# Sheet1.net
KiCad netlist of a schematic drawn in Altium Designer
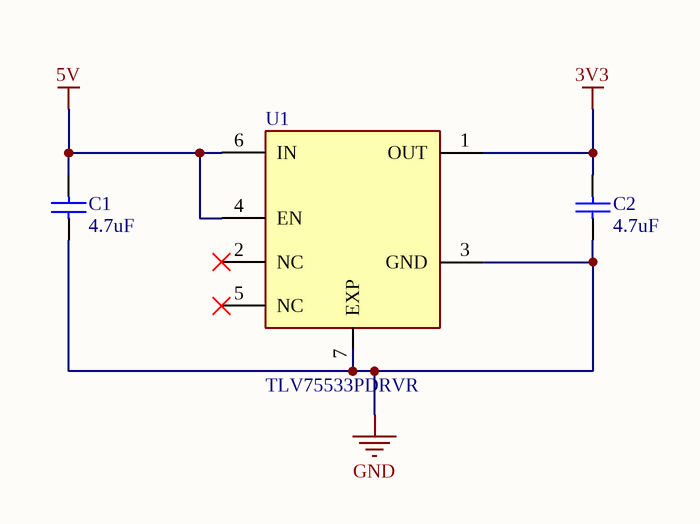
[diagram p0: Sheet1.SchDoc]

(export (version "E")
  (design (tool "Eeschema 10.0.6"))
  (components
    (comp (ref "C1")
      (value "4.7uF")
      (footprint "CAP_0402")
      (description "Capacitor SMD 0402 Generic, X5R or X7R")
      (libsource (lib "AndreiLib") (part "CAP_0402"))
    )
    (comp (ref "C2")
      (value "4.7uF")
      (footprint "CAP_0402")
      (description "Capacitor SMD 0402 Generic, X5R or X7R")
      (libsource (lib "AndreiLib") (part "CAP_0402"))
    )
    (comp (ref "U1")
      (value "TLV75533PDRVR")
      (footprint "TLV75533PDRVR")
      (description "500mA high-PSRR low-IQ low-dropout voltage regulator with enable 6-WSON -40 to 125")
      (fields (field (name "MANUFACTURER") "Texas Instruments"))
      (libsource (lib "AndreiLib") (part "TLV75533PDRVR"))
    )
  )
  (nets
    (net (code "1") (name "3V3") (class "Default")
      (node (ref "C2") (pin "2") (pintype "passive"))
      (node (ref "U1") (pin "1") (pinfunction "OUT_1") (pintype "passive"))
    )
    (net (code "2") (name "5V") (class "Default")
      (node (ref "C1") (pin "1") (pintype "passive"))
      (node (ref "U1") (pin "4") (pinfunction "EN_4") (pintype "passive"))
      (node (ref "U1") (pin "6") (pinfunction "IN_6") (pintype "passive"))
    )
    (net (code "3") (name "GND") (class "Default")
      (node (ref "C1") (pin "2") (pintype "passive"))
      (node (ref "C2") (pin "1") (pintype "passive"))
      (node (ref "U1") (pin "3") (pinfunction "GND_3") (pintype "power_in"))
      (node (ref "U1") (pin "7") (pinfunction "EXP_7") (pintype "power_in"))
    )
    (net (code "4") (name "unconnected-(U1-NC-Pad2)") (class "Default")
      (node (ref "U1") (pin "2") (pinfunction "NC_2") (pintype "passive+no_connect"))
    )
    (net (code "5") (name "unconnected-(U1-NC-Pad5)") (class "Default")
      (node (ref "U1") (pin "5") (pinfunction "NC_5") (pintype "passive+no_connect"))
    )
  )
)
